# og1_1.net
KiCad netlist of a schematic drawn in EAGLE
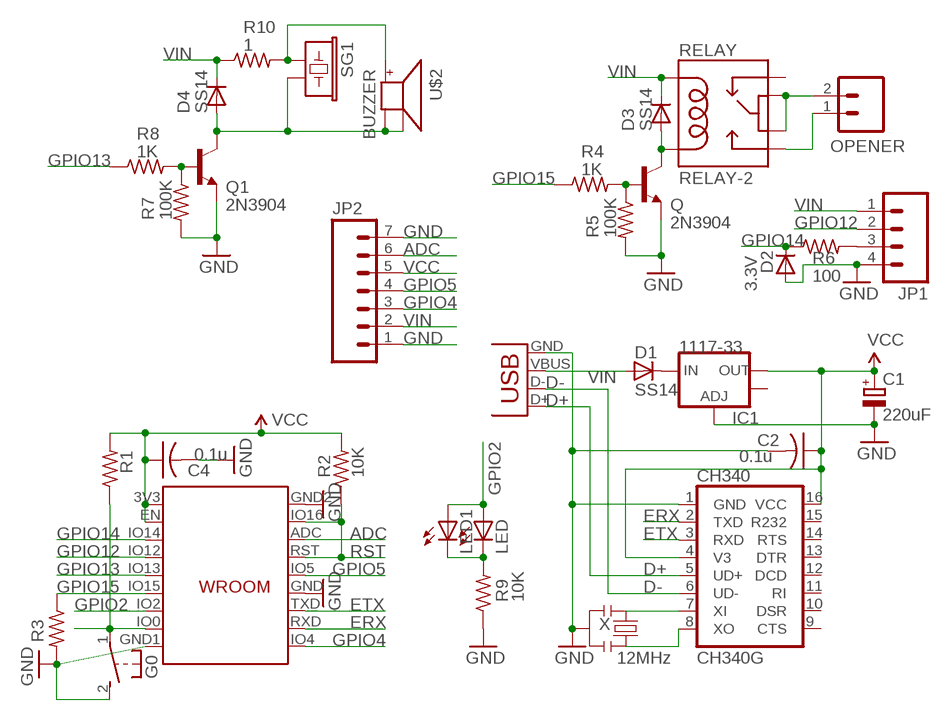
[diagram p0: schematic, sheet 1]

(export (version "E")
  (design (tool "Eeschema 10.0.6"))
  (components
    (comp (ref "C1")
      (value "220uF")
      (footprint "eagle-import:CT3528")
      (libsource (lib "eagle-import") (part "CPOL-EUCT3528"))
    )
    (comp (ref "C2")
      (value "0.1u")
      (footprint "eagle-import:C0603K")
      (libsource (lib "eagle-import") (part "C-USC0603K"))
    )
    (comp (ref "C4")
      (value "0.1u")
      (footprint "eagle-import:C0603K")
      (libsource (lib "eagle-import") (part "C-USC0603K"))
    )
    (comp (ref "CH340")
      (value "CH340G")
      (footprint "eagle-import:SO16")
      (libsource (lib "eagle-import") (part "CH340G"))
    )
    (comp (ref "D1")
      (value "SS14")
      (footprint "eagle-import:DO-214AC")
      (libsource (lib "eagle-import") (part "DIODE-DO-214AC"))
    )
    (comp (ref "D2")
      (value "3.3V")
      (footprint "eagle-import:MINIMELF")
      (libsource (lib "eagle-import") (part "DIODE-MINIMELF"))
    )
    (comp (ref "D3")
      (value "SS14")
      (footprint "eagle-import:DO-214AC")
      (libsource (lib "eagle-import") (part "DIODE-DO-214AC"))
    )
    (comp (ref "D4")
      (value "SS14")
      (footprint "eagle-import:DO-214AC")
      (libsource (lib "eagle-import") (part "DIODE-DO-214AC"))
    )
    (comp (ref "ESP")
      (value "WROOM02")
      (footprint "eagle-import:WROOM")
      (libsource (lib "eagle-import") (part "WROOM02"))
    )
    (comp (ref "G0")
      (value "31-XX")
      (footprint "eagle-import:B3F-31XX")
      (libsource (lib "eagle-import") (part "31-XX"))
    )
    (comp (ref "IC1")
      (value "1117-33")
      (footprint "eagle-import:SOT223")
      (libsource (lib "eagle-import") (part "V_REG_LM1117SOT223"))
    )
    (comp (ref "JP1")
      (value "M04SONIC")
      (footprint "eagle-import:1X04_SONICSENSOR")
      (libsource (lib "eagle-import") (part "M04SONIC"))
    )
    (comp (ref "JP2")
      (value "M07")
      (footprint "eagle-import:1X07")
      (libsource (lib "eagle-import") (part "M07"))
    )
    (comp (ref "LED")
      (value "LEDLED3MM_ABBRV")
      (footprint "eagle-import:LED3MM_ABBRV")
      (libsource (lib "eagle-import") (part "LEDLED3MM_ABBRV"))
    )
    (comp (ref "LED1")
      (value "LEDCHIPLED_0805")
      (footprint "eagle-import:CHIPLED_0805")
      (libsource (lib "eagle-import") (part "LEDCHIPLED_0805"))
    )
    (comp (ref "OPENER")
      (value "OPENER")
      (footprint "eagle-import:SCREWTERMINAL-4MM-2-X")
      (libsource (lib "eagle-import") (part "M024MM-X"))
    )
    (comp (ref "Q")
      (value "2N3904")
      (footprint "eagle-import:SOT23-3")
      (libsource (lib "eagle-import") (part "TRANSISTOR_NPNSOT23-3"))
    )
    (comp (ref "Q1")
      (value "2N3904")
      (footprint "eagle-import:SOT23-3")
      (libsource (lib "eagle-import") (part "TRANSISTOR_NPNSOT23-3"))
    )
    (comp (ref "R1")
      (value "10K")
      (footprint "eagle-import:R0603")
      (libsource (lib "eagle-import") (part "R-US_R0603"))
    )
    (comp (ref "R2")
      (value "10K")
      (footprint "eagle-import:R0603")
      (libsource (lib "eagle-import") (part "R-US_R0603"))
    )
    (comp (ref "R3")
      (value "10K")
      (footprint "eagle-import:R0603")
      (libsource (lib "eagle-import") (part "R-US_R0603"))
    )
    (comp (ref "R4")
      (value "1K")
      (footprint "eagle-import:R0603")
      (libsource (lib "eagle-import") (part "adafruit2013_R-US_R0603"))
    )
    (comp (ref "R5")
      (value "100K")
      (footprint "eagle-import:R0603")
      (libsource (lib "eagle-import") (part "adafruit2013_R-US_R0603"))
    )
    (comp (ref "R6")
      (value "100")
      (footprint "eagle-import:R0603")
      (libsource (lib "eagle-import") (part "adafruit2013_R-US_R0603"))
    )
    (comp (ref "R7")
      (value "100K")
      (footprint "eagle-import:R0603")
      (libsource (lib "eagle-import") (part "adafruit2013_R-US_R0603"))
    )
    (comp (ref "R8")
      (value "1K")
      (footprint "eagle-import:R0603")
      (libsource (lib "eagle-import") (part "adafruit2013_R-US_R0603"))
    )
    (comp (ref "R9")
      (value "10K")
      (footprint "eagle-import:R0603")
      (libsource (lib "eagle-import") (part "R-US_R0603"))
    )
    (comp (ref "R10")
      (value "1")
      (footprint "eagle-import:R0603")
      (libsource (lib "eagle-import") (part "adafruit2013_R-US_R0603"))
    )
    (comp (ref "RELAY")
      (value "RELAY-2")
      (footprint "eagle-import:RELAY-HK4100F")
      (libsource (lib "eagle-import") (part "RELAY-2"))
    )
    (comp (ref "SG1")
      (value "BUZZERPTH")
      (footprint "eagle-import:BUZZER-12MM")
      (libsource (lib "eagle-import") (part "BUZZERPTH"))
    )
    (comp (ref "U$2")
      (value "BUZZER")
      (footprint "eagle-import:SMT-8585-BUZZER")
      (libsource (lib "eagle-import") (part "BUZZER"))
    )
    (comp (ref "X")
      (value "12MHz")
      (footprint "eagle-import:RESONATOR-SMD")
      (libsource (lib "eagle-import") (part "RESONATORSMD"))
    )
    (comp (ref "X3")
      (value "USB-MICROB")
      (footprint "eagle-import:USB-MICROB")
      (libsource (lib "eagle-import") (part "USB-MICROB"))
    )
  )
  (nets
    (net (code "1") (name "/ADC") (class "Default")
      (node (ref "ESP") (pin "ADC") (pinfunction "ADC_ADC") (pintype "bidirectional"))
      (node (ref "JP2") (pin "6") (pinfunction "6_6") (pintype "passive"))
    )
    (net (code "2") (name "/D+") (class "Default")
      (node (ref "CH340") (pin "5") (pinfunction "UD+_5") (pintype "bidirectional"))
      (node (ref "X3") (pin "D+") (pinfunction "D+_D+") (pintype "bidirectional"))
    )
    (net (code "3") (name "/D-") (class "Default")
      (node (ref "CH340") (pin "6") (pinfunction "UD-_6") (pintype "bidirectional"))
      (node (ref "X3") (pin "D-") (pinfunction "D-_D-") (pintype "bidirectional"))
    )
    (net (code "4") (name "/ERX") (class "Default")
      (node (ref "CH340") (pin "2") (pinfunction "TXD_2") (pintype "bidirectional"))
      (node (ref "ESP") (pin "RXD") (pinfunction "RX_RXD") (pintype "bidirectional"))
    )
    (net (code "5") (name "/ETX") (class "Default")
      (node (ref "CH340") (pin "3") (pinfunction "RXD_3") (pintype "bidirectional"))
      (node (ref "ESP") (pin "TXD") (pinfunction "TX_TXD") (pintype "bidirectional"))
    )
    (net (code "6") (name "/GPIO2") (class "Default")
      (node (ref "ESP") (pin "IO2") (pinfunction "IO2_IO2") (pintype "bidirectional"))
      (node (ref "LED") (pin "A") (pinfunction "A_A") (pintype "passive"))
      (node (ref "LED1") (pin "A") (pinfunction "A_A") (pintype "passive"))
    )
    (net (code "7") (name "/GPIO4") (class "Default")
      (node (ref "ESP") (pin "IO4") (pinfunction "IO4_IO4") (pintype "bidirectional"))
      (node (ref "JP2") (pin "3") (pinfunction "3_3") (pintype "passive"))
    )
    (net (code "8") (name "/GPIO5") (class "Default")
      (node (ref "ESP") (pin "IO5") (pinfunction "IO5_IO5") (pintype "bidirectional"))
      (node (ref "JP2") (pin "4") (pinfunction "4_4") (pintype "passive"))
    )
    (net (code "9") (name "/GPIO12") (class "Default")
      (node (ref "ESP") (pin "IO12") (pinfunction "IO12_IO12") (pintype "bidirectional"))
      (node (ref "JP1") (pin "2") (pinfunction "2_2") (pintype "passive"))
    )
    (net (code "10") (name "/GPIO13") (class "Default")
      (node (ref "ESP") (pin "IO13") (pinfunction "IO13_IO13") (pintype "bidirectional"))
      (node (ref "R8") (pin "1") (pinfunction "1_1") (pintype "passive"))
    )
    (net (code "11") (name "/GPIO14") (class "Default")
      (node (ref "D2") (pin "C") (pinfunction "C_C") (pintype "passive"))
      (node (ref "ESP") (pin "IO14") (pinfunction "IO14_IO14") (pintype "bidirectional"))
      (node (ref "R6") (pin "1") (pinfunction "1_1") (pintype "passive"))
    )
    (net (code "12") (name "/GPIO15") (class "Default")
      (node (ref "ESP") (pin "IO15") (pinfunction "IO15_IO15") (pintype "bidirectional"))
      (node (ref "R3") (pin "1") (pinfunction "1_1") (pintype "passive"))
      (node (ref "R4") (pin "1") (pinfunction "1_1") (pintype "passive"))
    )
    (net (code "13") (name "/RST") (class "Default")
      (node (ref "ESP") (pin "IO16") (pinfunction "IO16_IO16") (pintype "bidirectional"))
      (node (ref "ESP") (pin "RST") (pinfunction "RST_RST") (pintype "bidirectional"))
      (node (ref "R2") (pin "1") (pinfunction "1_1") (pintype "passive"))
    )
    (net (code "14") (name "/VIN") (class "Default")
      (node (ref "D1") (pin "A") (pinfunction "A_A") (pintype "passive"))
      (node (ref "D3") (pin "C") (pinfunction "C_C") (pintype "passive"))
      (node (ref "D4") (pin "C") (pinfunction "C_C") (pintype "passive"))
      (node (ref "JP1") (pin "1") (pinfunction "1_1") (pintype "passive"))
      (node (ref "JP2") (pin "2") (pinfunction "2_2") (pintype "passive"))
      (node (ref "R10") (pin "1") (pinfunction "1_1") (pintype "passive"))
      (node (ref "RELAY") (pin "2") (pinfunction "2_2") (pintype "bidirectional"))
      (node (ref "X3") (pin "VBUS") (pinfunction "VBUS_VBUS") (pintype "bidirectional"))
    )
    (net (code "15") (name "GND") (class "Default")
      (node (ref "C1") (pin "-") (pinfunction "-_-") (pintype "passive"))
      (node (ref "C2") (pin "2") (pinfunction "2_2") (pintype "passive"))
      (node (ref "C4") (pin "2") (pinfunction "2_2") (pintype "passive"))
      (node (ref "CH340") (pin "1") (pinfunction "GND_1") (pintype "power_in"))
      (node (ref "D2") (pin "A") (pinfunction "A_A") (pintype "passive"))
      (node (ref "ESP") (pin "GND") (pinfunction "GND_GND") (pintype "power_in"))
      (node (ref "ESP") (pin "GND1") (pinfunction "GND1_GND1") (pintype "power_in"))
      (node (ref "ESP") (pin "GND2") (pinfunction "GND2_GND2") (pintype "power_in"))
      (node (ref "G0") (pin "2") (pinfunction "S_2") (pintype "passive"))
      (node (ref "IC1") (pin "1") (pinfunction "ADJ_1") (pintype "input"))
      (node (ref "JP1") (pin "4") (pinfunction "4_4") (pintype "passive"))
      (node (ref "JP2") (pin "1") (pinfunction "1_1") (pintype "passive"))
      (node (ref "JP2") (pin "7") (pinfunction "7_7") (pintype "passive"))
      (node (ref "Q") (pin "2") (pinfunction "E_2") (pintype "passive"))
      (node (ref "Q1") (pin "2") (pinfunction "E_2") (pintype "passive"))
      (node (ref "R3") (pin "2") (pinfunction "2_2") (pintype "passive"))
      (node (ref "R5") (pin "2") (pinfunction "2_2") (pintype "passive"))
      (node (ref "R7") (pin "2") (pinfunction "2_2") (pintype "passive"))
      (node (ref "R9") (pin "1") (pinfunction "1_1") (pintype "passive"))
      (node (ref "X") (pin "2") (pinfunction "2_2") (pintype "passive"))
      (node (ref "X3") (pin "GND") (pinfunction "GND_GND") (pintype "bidirectional"))
    )
    (net (code "16") (name "Net-(CH340-XI)") (class "Default")
      (node (ref "CH340") (pin "7") (pinfunction "XI_7") (pintype "bidirectional"))
      (node (ref "X") (pin "1") (pinfunction "1_1") (pintype "passive"))
    )
    (net (code "17") (name "Net-(CH340-XO)") (class "Default")
      (node (ref "CH340") (pin "8") (pinfunction "XO_8") (pintype "bidirectional"))
      (node (ref "X") (pin "3") (pinfunction "3_3") (pintype "passive"))
    )
    (net (code "18") (name "Net-(G0-P)") (class "Default")
      (node (ref "ESP") (pin "IO0") (pinfunction "IO0_IO0") (pintype "bidirectional"))
      (node (ref "G0") (pin "1") (pinfunction "P_1") (pintype "passive"))
      (node (ref "R1") (pin "1") (pinfunction "1_1") (pintype "passive"))
    )
    (net (code "19") (name "Net-(IC1-IN)") (class "Default")
      (node (ref "D1") (pin "C") (pinfunction "C_C") (pintype "passive"))
      (node (ref "IC1") (pin "3") (pinfunction "IN_3") (pintype "input"))
    )
    (net (code "20") (name "Net-(JP1-Pad3)") (class "Default")
      (node (ref "JP1") (pin "3") (pinfunction "3_3") (pintype "passive"))
      (node (ref "R6") (pin "2") (pinfunction "2_2") (pintype "passive"))
    )
    (net (code "21") (name "Net-(LED-C)") (class "Default")
      (node (ref "LED") (pin "K") (pinfunction "C_K") (pintype "passive"))
      (node (ref "LED1") (pin "C") (pinfunction "C_C") (pintype "passive"))
      (node (ref "R9") (pin "2") (pinfunction "2_2") (pintype "passive"))
    )
    (net (code "22") (name "Net-(OPENER-Pad1)") (class "Default")
      (node (ref "OPENER") (pin "1") (pinfunction "1_1") (pintype "passive"))
      (node (ref "RELAY") (pin "10") (pinfunction "10_10") (pintype "bidirectional"))
    )
    (net (code "23") (name "Net-(OPENER-Pad2)") (class "Default")
      (node (ref "OPENER") (pin "2") (pinfunction "2_2") (pintype "passive"))
      (node (ref "RELAY") (pin "5") (pinfunction "5_5") (pintype "bidirectional"))
      (node (ref "RELAY") (pin "6") (pinfunction "6_6") (pintype "bidirectional"))
    )
    (net (code "24") (name "Net-(Q-B)") (class "Default")
      (node (ref "Q") (pin "1") (pinfunction "B_1") (pintype "passive"))
      (node (ref "R4") (pin "2") (pinfunction "2_2") (pintype "passive"))
      (node (ref "R5") (pin "1") (pinfunction "1_1") (pintype "passive"))
    )
    (net (code "25") (name "Net-(Q-C)") (class "Default")
      (node (ref "D3") (pin "A") (pinfunction "A_A") (pintype "passive"))
      (node (ref "Q") (pin "3") (pinfunction "C_3") (pintype "passive"))
      (node (ref "RELAY") (pin "9") (pinfunction "9_9") (pintype "bidirectional"))
    )
    (net (code "26") (name "Net-(Q1-B)") (class "Default")
      (node (ref "Q1") (pin "1") (pinfunction "B_1") (pintype "passive"))
      (node (ref "R7") (pin "1") (pinfunction "1_1") (pintype "passive"))
      (node (ref "R8") (pin "2") (pinfunction "2_2") (pintype "passive"))
    )
    (net (code "27") (name "Net-(Q1-C)") (class "Default")
      (node (ref "D4") (pin "A") (pinfunction "A_A") (pintype "passive"))
      (node (ref "Q1") (pin "3") (pinfunction "C_3") (pintype "passive"))
      (node (ref "SG1") (pin "-") (pinfunction "2_-") (pintype "passive"))
      (node (ref "U$2") (pin "-") (pinfunction "-_-") (pintype "passive"))
      (node (ref "U$2") (pin "A-") (pinfunction "A-_A-") (pintype "passive"))
    )
    (net (code "28") (name "Net-(SG1-1)") (class "Default")
      (node (ref "R10") (pin "2") (pinfunction "2_2") (pintype "passive"))
      (node (ref "SG1") (pin "+") (pinfunction "1_+") (pintype "passive"))
      (node (ref "U$2") (pin "+") (pinfunction "+_+") (pintype "passive"))
    )
    (net (code "29") (name "VCC") (class "Default")
      (node (ref "C1") (pin "+") (pinfunction "+_+") (pintype "passive"))
      (node (ref "C2") (pin "1") (pinfunction "1_1") (pintype "passive"))
      (node (ref "C4") (pin "1") (pinfunction "1_1") (pintype "passive"))
      (node (ref "CH340") (pin "16") (pinfunction "VCC_16") (pintype "power_in"))
      (node (ref "CH340") (pin "4") (pinfunction "V3_4") (pintype "bidirectional"))
      (node (ref "ESP") (pin "3V3") (pinfunction "VCC_3V3") (pintype "power_in"))
      (node (ref "ESP") (pin "EN") (pinfunction "EN_EN") (pintype "bidirectional"))
      (node (ref "IC1") (pin "2") (pinfunction "OUT_2") (pintype "bidirectional"))
      (node (ref "JP2") (pin "5") (pinfunction "5_5") (pintype "passive"))
      (node (ref "R1") (pin "2") (pinfunction "2_2") (pintype "passive"))
      (node (ref "R2") (pin "2") (pinfunction "2_2") (pintype "passive"))
    )
    (net (code "30") (name "unconnected-(CH340-CTS-Pad9)") (class "Default")
      (node (ref "CH340") (pin "9") (pinfunction "CTS_9") (pintype "bidirectional"))
    )
    (net (code "31") (name "unconnected-(CH340-DCD-Pad12)") (class "Default")
      (node (ref "CH340") (pin "12") (pinfunction "DCD_12") (pintype "bidirectional"))
    )
    (net (code "32") (name "unconnected-(CH340-DSR-Pad10)") (class "Default")
      (node (ref "CH340") (pin "10") (pinfunction "DSR_10") (pintype "bidirectional"))
    )
    (net (code "33") (name "unconnected-(CH340-DTR-Pad13)") (class "Default")
      (node (ref "CH340") (pin "13") (pinfunction "DTR_13") (pintype "bidirectional"))
    )
    (net (code "34") (name "unconnected-(CH340-R232-Pad15)") (class "Default")
      (node (ref "CH340") (pin "15") (pinfunction "R232_15") (pintype "bidirectional"))
    )
    (net (code "35") (name "unconnected-(CH340-RI-Pad11)") (class "Default")
      (node (ref "CH340") (pin "11") (pinfunction "RI_11") (pintype "bidirectional"))
    )
    (net (code "36") (name "unconnected-(CH340-RTS-Pad14)") (class "Default")
      (node (ref "CH340") (pin "14") (pinfunction "RTS_14") (pintype "bidirectional"))
    )
    (net (code "37") (name "unconnected-(IC1-OUT-Pad4)") (class "Default")
      (node (ref "IC1") (pin "4") (pinfunction "OUT_4") (pintype "bidirectional"))
    )
    (net (code "38") (name "unconnected-(RELAY-Pad1)") (class "Default")
      (node (ref "RELAY") (pin "1") (pinfunction "1_1") (pintype "bidirectional"))
    )
  )
)
